# STM32L05C8T6.net
KiCad netlist of a schematic drawn in EAGLE
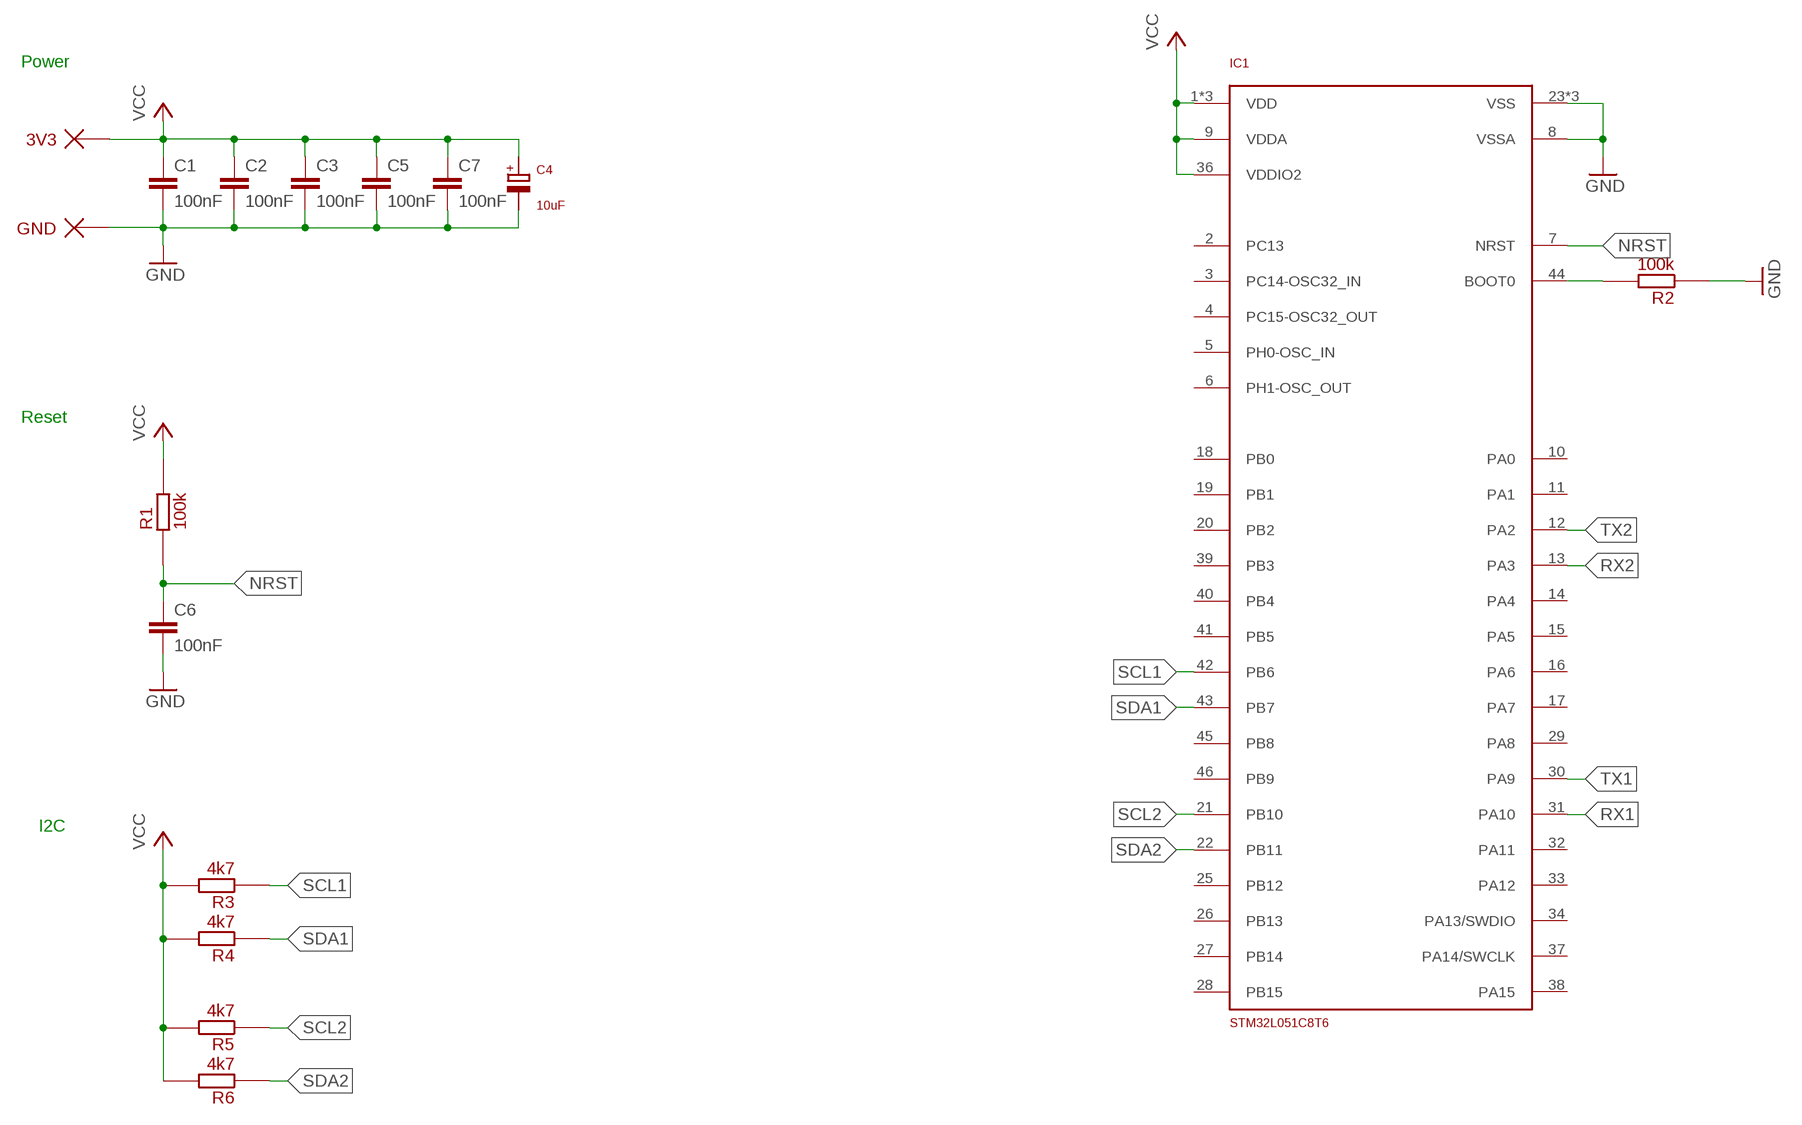
[diagram p0: schematic, sheet 1]

(export (version "E")
  (design (tool "Eeschema 10.0.6"))
  (components
    (comp (ref "C1")
      (value "100nF")
      (footprint "eagle-import:C1206")
      (libsource (lib "eagle-import") (part "SMD-C-1206"))
    )
    (comp (ref "C2")
      (value "100nF")
      (footprint "eagle-import:C1206")
      (libsource (lib "eagle-import") (part "SMD-C-1206"))
    )
    (comp (ref "C3")
      (value "100nF")
      (footprint "eagle-import:C1206")
      (libsource (lib "eagle-import") (part "SMD-C-1206"))
    )
    (comp (ref "C4")
      (value "10uF")
      (footprint "eagle-import:SANYO-OSCON_SMD_A5")
      (libsource (lib "eagle-import") (part "SMD-ELKOA5"))
    )
    (comp (ref "C5")
      (value "100nF")
      (footprint "eagle-import:C1206")
      (libsource (lib "eagle-import") (part "SMD-C-1206"))
    )
    (comp (ref "C6")
      (value "100nF")
      (footprint "eagle-import:C1206")
      (libsource (lib "eagle-import") (part "SMD-C-1206"))
    )
    (comp (ref "C7")
      (value "100nF")
      (footprint "eagle-import:C1206")
      (libsource (lib "eagle-import") (part "SMD-C-1206"))
    )
    (comp (ref "IC1")
      (value "STM32L051C8T6")
      (footprint "eagle-import:TQFP48_7X7")
      (libsource (lib "eagle-import") (part "STM32L051C8T6"))
    )
    (comp (ref "P1")
      (value "3V3")
      (footprint "eagle-import:PIN")
      (libsource (lib "eagle-import") (part "PIN"))
    )
    (comp (ref "P2")
      (value "GND")
      (footprint "eagle-import:PIN")
      (libsource (lib "eagle-import") (part "PIN"))
    )
    (comp (ref "R1")
      (value "100k")
      (footprint "eagle-import:R0603")
      (libsource (lib "eagle-import") (part "SMD-RR0603"))
    )
    (comp (ref "R2")
      (value "100k")
      (footprint "eagle-import:R0603")
      (libsource (lib "eagle-import") (part "SMD-RR0603"))
    )
    (comp (ref "R3")
      (value "4k7")
      (footprint "eagle-import:R0603")
      (libsource (lib "eagle-import") (part "SMD-RR0603"))
    )
    (comp (ref "R4")
      (value "4k7")
      (footprint "eagle-import:R0603")
      (libsource (lib "eagle-import") (part "SMD-RR0603"))
    )
    (comp (ref "R5")
      (value "4k7")
      (footprint "eagle-import:R0603")
      (libsource (lib "eagle-import") (part "SMD-RR0603"))
    )
    (comp (ref "R6")
      (value "4k7")
      (footprint "eagle-import:R0603")
      (libsource (lib "eagle-import") (part "SMD-RR0603"))
    )
  )
  (nets
    (net (code "1") (name "GND") (class "Default")
      (node (ref "C1") (pin "2") (pinfunction "2_2") (pintype "passive"))
      (node (ref "C2") (pin "2") (pinfunction "2_2") (pintype "passive"))
      (node (ref "C3") (pin "2") (pinfunction "2_2") (pintype "passive"))
      (node (ref "C4") (pin "-") (pinfunction "P$2_-") (pintype "passive"))
      (node (ref "C5") (pin "2") (pinfunction "2_2") (pintype "passive"))
      (node (ref "C6") (pin "2") (pinfunction "2_2") (pintype "passive"))
      (node (ref "C7") (pin "2") (pinfunction "2_2") (pintype "passive"))
      (node (ref "IC1") (pin "23") (pinfunction "VSS_23") (pintype "bidirectional"))
      (node (ref "IC1") (pin "35") (pinfunction "VSS_35") (pintype "bidirectional"))
      (node (ref "IC1") (pin "47") (pinfunction "VSS_47") (pintype "bidirectional"))
      (node (ref "IC1") (pin "8") (pinfunction "VSSA_8") (pintype "bidirectional"))
      (node (ref "P2") (pin "P$1") (pinfunction "P$1_P$1") (pintype "bidirectional"))
      (node (ref "R2") (pin "1") (pinfunction "P$1_1") (pintype "passive"))
    )
    (net (code "2") (name "NRST") (class "Default")
      (node (ref "C6") (pin "1") (pinfunction "1_1") (pintype "passive"))
      (node (ref "IC1") (pin "7") (pinfunction "NRST_7") (pintype "bidirectional"))
      (node (ref "R1") (pin "1") (pinfunction "P$1_1") (pintype "passive"))
    )
    (net (code "3") (name "Net-(IC1-BOOT0)") (class "Default")
      (node (ref "IC1") (pin "44") (pinfunction "BOOT0_44") (pintype "bidirectional"))
      (node (ref "R2") (pin "2") (pinfunction "P$3_2") (pintype "passive"))
    )
    (net (code "4") (name "RX1") (class "Default")
      (node (ref "IC1") (pin "31") (pinfunction "PA10_31") (pintype "bidirectional"))
    )
    (net (code "5") (name "RX2") (class "Default")
      (node (ref "IC1") (pin "13") (pinfunction "PA3_13") (pintype "bidirectional"))
    )
    (net (code "6") (name "SCL1") (class "Default")
      (node (ref "IC1") (pin "42") (pinfunction "PB6_42") (pintype "bidirectional"))
      (node (ref "R3") (pin "1") (pinfunction "P$1_1") (pintype "passive"))
    )
    (net (code "7") (name "SCL2") (class "Default")
      (node (ref "IC1") (pin "21") (pinfunction "PB10_21") (pintype "bidirectional"))
      (node (ref "R5") (pin "1") (pinfunction "P$1_1") (pintype "passive"))
    )
    (net (code "8") (name "SDA1") (class "Default")
      (node (ref "IC1") (pin "43") (pinfunction "PB7_43") (pintype "bidirectional"))
      (node (ref "R4") (pin "1") (pinfunction "P$1_1") (pintype "passive"))
    )
    (net (code "9") (name "SDA2") (class "Default")
      (node (ref "IC1") (pin "22") (pinfunction "PB11_22") (pintype "bidirectional"))
      (node (ref "R6") (pin "1") (pinfunction "P$1_1") (pintype "passive"))
    )
    (net (code "10") (name "TX1") (class "Default")
      (node (ref "IC1") (pin "30") (pinfunction "PA9_30") (pintype "bidirectional"))
    )
    (net (code "11") (name "TX2") (class "Default")
      (node (ref "IC1") (pin "12") (pinfunction "PA2_12") (pintype "bidirectional"))
    )
    (net (code "12") (name "VCC") (class "Default")
      (node (ref "C1") (pin "1") (pinfunction "1_1") (pintype "passive"))
      (node (ref "C2") (pin "1") (pinfunction "1_1") (pintype "passive"))
      (node (ref "C3") (pin "1") (pinfunction "1_1") (pintype "passive"))
      (node (ref "C4") (pin "+") (pinfunction "P$1_+") (pintype "passive"))
      (node (ref "C5") (pin "1") (pinfunction "1_1") (pintype "passive"))
      (node (ref "C7") (pin "1") (pinfunction "1_1") (pintype "passive"))
      (node (ref "IC1") (pin "1") (pinfunction "VDD_1") (pintype "bidirectional"))
      (node (ref "IC1") (pin "24") (pinfunction "VDD_24") (pintype "bidirectional"))
      (node (ref "IC1") (pin "36") (pinfunction "VDDIO2_36") (pintype "bidirectional"))
      (node (ref "IC1") (pin "48") (pinfunction "VDD_48") (pintype "bidirectional"))
      (node (ref "IC1") (pin "9") (pinfunction "VDDA_9") (pintype "bidirectional"))
      (node (ref "P1") (pin "P$1") (pinfunction "P$1_P$1") (pintype "bidirectional"))
      (node (ref "R1") (pin "2") (pinfunction "P$3_2") (pintype "passive"))
      (node (ref "R3") (pin "2") (pinfunction "P$3_2") (pintype "passive"))
      (node (ref "R4") (pin "2") (pinfunction "P$3_2") (pintype "passive"))
      (node (ref "R5") (pin "2") (pinfunction "P$3_2") (pintype "passive"))
      (node (ref "R6") (pin "2") (pinfunction "P$3_2") (pintype "passive"))
    )
    (net (code "13") (name "unconnected-(IC1-PA0-Pad10)") (class "Default")
      (node (ref "IC1") (pin "10") (pinfunction "PA0_10") (pintype "bidirectional"))
    )
    (net (code "14") (name "unconnected-(IC1-PA1-Pad11)") (class "Default")
      (node (ref "IC1") (pin "11") (pinfunction "PA1_11") (pintype "bidirectional"))
    )
    (net (code "15") (name "unconnected-(IC1-PA4-Pad14)") (class "Default")
      (node (ref "IC1") (pin "14") (pinfunction "PA4_14") (pintype "bidirectional"))
    )
    (net (code "16") (name "unconnected-(IC1-PA5-Pad15)") (class "Default")
      (node (ref "IC1") (pin "15") (pinfunction "PA5_15") (pintype "bidirectional"))
    )
    (net (code "17") (name "unconnected-(IC1-PA6-Pad16)") (class "Default")
      (node (ref "IC1") (pin "16") (pinfunction "PA6_16") (pintype "bidirectional"))
    )
    (net (code "18") (name "unconnected-(IC1-PA7-Pad17)") (class "Default")
      (node (ref "IC1") (pin "17") (pinfunction "PA7_17") (pintype "bidirectional"))
    )
    (net (code "19") (name "unconnected-(IC1-PA8-Pad29)") (class "Default")
      (node (ref "IC1") (pin "29") (pinfunction "PA8_29") (pintype "bidirectional"))
    )
    (net (code "20") (name "unconnected-(IC1-PA11-Pad32)") (class "Default")
      (node (ref "IC1") (pin "32") (pinfunction "PA11_32") (pintype "bidirectional"))
    )
    (net (code "21") (name "unconnected-(IC1-PA12-Pad33)") (class "Default")
      (node (ref "IC1") (pin "33") (pinfunction "PA12_33") (pintype "bidirectional"))
    )
    (net (code "22") (name "unconnected-(IC1-PA13{slash}SWDIO-Pad34)") (class "Default")
      (node (ref "IC1") (pin "34") (pinfunction "PA13/SWDIO_34") (pintype "bidirectional"))
    )
    (net (code "23") (name "unconnected-(IC1-PA14{slash}SWCLK-Pad37)") (class "Default")
      (node (ref "IC1") (pin "37") (pinfunction "PA14/SWCLK_37") (pintype "bidirectional"))
    )
    (net (code "24") (name "unconnected-(IC1-PA15-Pad38)") (class "Default")
      (node (ref "IC1") (pin "38") (pinfunction "PA15_38") (pintype "bidirectional"))
    )
    (net (code "25") (name "unconnected-(IC1-PB0-Pad18)") (class "Default")
      (node (ref "IC1") (pin "18") (pinfunction "PB0_18") (pintype "bidirectional"))
    )
    (net (code "26") (name "unconnected-(IC1-PB1-Pad19)") (class "Default")
      (node (ref "IC1") (pin "19") (pinfunction "PB1_19") (pintype "bidirectional"))
    )
    (net (code "27") (name "unconnected-(IC1-PB2-Pad20)") (class "Default")
      (node (ref "IC1") (pin "20") (pinfunction "PB2_20") (pintype "bidirectional"))
    )
    (net (code "28") (name "unconnected-(IC1-PB3-Pad39)") (class "Default")
      (node (ref "IC1") (pin "39") (pinfunction "PB3_39") (pintype "bidirectional"))
    )
    (net (code "29") (name "unconnected-(IC1-PB4-Pad40)") (class "Default")
      (node (ref "IC1") (pin "40") (pinfunction "PB4_40") (pintype "bidirectional"))
    )
    (net (code "30") (name "unconnected-(IC1-PB5-Pad41)") (class "Default")
      (node (ref "IC1") (pin "41") (pinfunction "PB5_41") (pintype "bidirectional"))
    )
    (net (code "31") (name "unconnected-(IC1-PB8-Pad45)") (class "Default")
      (node (ref "IC1") (pin "45") (pinfunction "PB8_45") (pintype "bidirectional"))
    )
    (net (code "32") (name "unconnected-(IC1-PB9-Pad46)") (class "Default")
      (node (ref "IC1") (pin "46") (pinfunction "PB9_46") (pintype "bidirectional"))
    )
    (net (code "33") (name "unconnected-(IC1-PB12-Pad25)") (class "Default")
      (node (ref "IC1") (pin "25") (pinfunction "PB12_25") (pintype "bidirectional"))
    )
    (net (code "34") (name "unconnected-(IC1-PB13-Pad26)") (class "Default")
      (node (ref "IC1") (pin "26") (pinfunction "PB13_26") (pintype "bidirectional"))
    )
    (net (code "35") (name "unconnected-(IC1-PB14-Pad27)") (class "Default")
      (node (ref "IC1") (pin "27") (pinfunction "PB14_27") (pintype "bidirectional"))
    )
    (net (code "36") (name "unconnected-(IC1-PB15-Pad28)") (class "Default")
      (node (ref "IC1") (pin "28") (pinfunction "PB15_28") (pintype "bidirectional"))
    )
    (net (code "37") (name "unconnected-(IC1-PC13-Pad2)") (class "Default")
      (node (ref "IC1") (pin "2") (pinfunction "PC13_2") (pintype "bidirectional"))
    )
    (net (code "38") (name "unconnected-(IC1-PC14-OSC32_IN-Pad3)") (class "Default")
      (node (ref "IC1") (pin "3") (pinfunction "PC14-OSC32_IN_3") (pintype "bidirectional"))
    )
    (net (code "39") (name "unconnected-(IC1-PC15-OSC32_OUT-Pad4)") (class "Default")
      (node (ref "IC1") (pin "4") (pinfunction "PC15-OSC32_OUT_4") (pintype "bidirectional"))
    )
    (net (code "40") (name "unconnected-(IC1-PH0-OSC_IN-Pad5)") (class "Default")
      (node (ref "IC1") (pin "5") (pinfunction "PH0-OSC_IN_5") (pintype "bidirectional"))
    )
    (net (code "41") (name "unconnected-(IC1-PH1-OSC_OUT-Pad6)") (class "Default")
      (node (ref "IC1") (pin "6") (pinfunction "PH1-OSC_OUT_6") (pintype "bidirectional"))
    )
  )
)
